# mux.net
KiCad netlist of a schematic drawn in Altium Designer
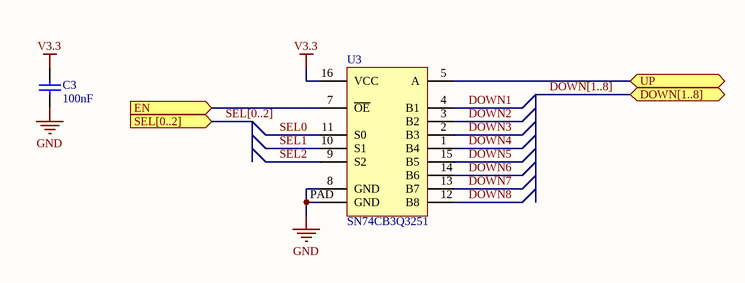
[diagram p0: mux.SchDoc]

(export (version "E")
  (design (tool "Eeschema 10.0.6"))
  (components
    (comp (ref "C3") (value "100nF") (footprint "0402") (libsource (lib "misc") (part "Capacitor")))
    (comp (ref "U3")
      (value "SN74CB3Q3251")
      (footprint "TI_RGY")
      (description "1:8 Mux")
      (libsource (lib "misc") (part "SN74CB3Q3251"))
    )
  )
  (nets
    (net (code "1") (name "/DOWN1") (class "Default")
      (node (ref "U3") (pin "4") (pinfunction "B1_4") (pintype "passive"))
    )
    (net (code "2") (name "/DOWN2") (class "Default")
      (node (ref "U3") (pin "3") (pinfunction "B2_3") (pintype "passive"))
    )
    (net (code "3") (name "/DOWN3") (class "Default")
      (node (ref "U3") (pin "2") (pinfunction "B3_2") (pintype "passive"))
    )
    (net (code "4") (name "/DOWN4") (class "Default")
      (node (ref "U3") (pin "1") (pinfunction "B4_1") (pintype "passive"))
    )
    (net (code "5") (name "/DOWN5") (class "Default")
      (node (ref "U3") (pin "15") (pinfunction "B5_15") (pintype "passive"))
    )
    (net (code "6") (name "/DOWN6") (class "Default")
      (node (ref "U3") (pin "14") (pinfunction "B6_14") (pintype "passive"))
    )
    (net (code "7") (name "/DOWN7") (class "Default")
      (node (ref "U3") (pin "13") (pinfunction "B7_13") (pintype "passive"))
    )
    (net (code "8") (name "/DOWN8") (class "Default")
      (node (ref "U3") (pin "12") (pinfunction "B8_12") (pintype "passive"))
    )
    (net (code "10") (name "/EN") (class "Default")
      (node (ref "U3") (pin "7") (pinfunction "~{OE}_7") (pintype "passive"))
    )
    (net (code "11") (name "/SEL0") (class "Default")
      (node (ref "U3") (pin "11") (pinfunction "S0_11") (pintype "passive"))
    )
    (net (code "12") (name "/SEL1") (class "Default")
      (node (ref "U3") (pin "10") (pinfunction "S1_10") (pintype "passive"))
    )
    (net (code "13") (name "/SEL2") (class "Default")
      (node (ref "U3") (pin "9") (pinfunction "S2_9") (pintype "passive"))
    )
    (net (code "15") (name "/UP") (class "Default")
      (node (ref "U3") (pin "5") (pinfunction "A_5") (pintype "passive"))
    )
    (net (code "16") (name "GND") (class "Default")
      (node (ref "C3") (pin "1") (pinfunction "1_1") (pintype "passive"))
      (node (ref "U3") (pin "8") (pinfunction "GND_8") (pintype "passive"))
      (node (ref "U3") (pin "PAD") (pinfunction "GND_PAD") (pintype "passive"))
    )
    (net (code "17") (name "V3.3") (class "Default")
      (node (ref "C3") (pin "2") (pinfunction "2_2") (pintype "passive"))
      (node (ref "U3") (pin "16") (pinfunction "VCC_16") (pintype "passive"))
    )
  )
)
